# XOrduino-v1.net
KiCad netlist of a schematic drawn in EAGLE
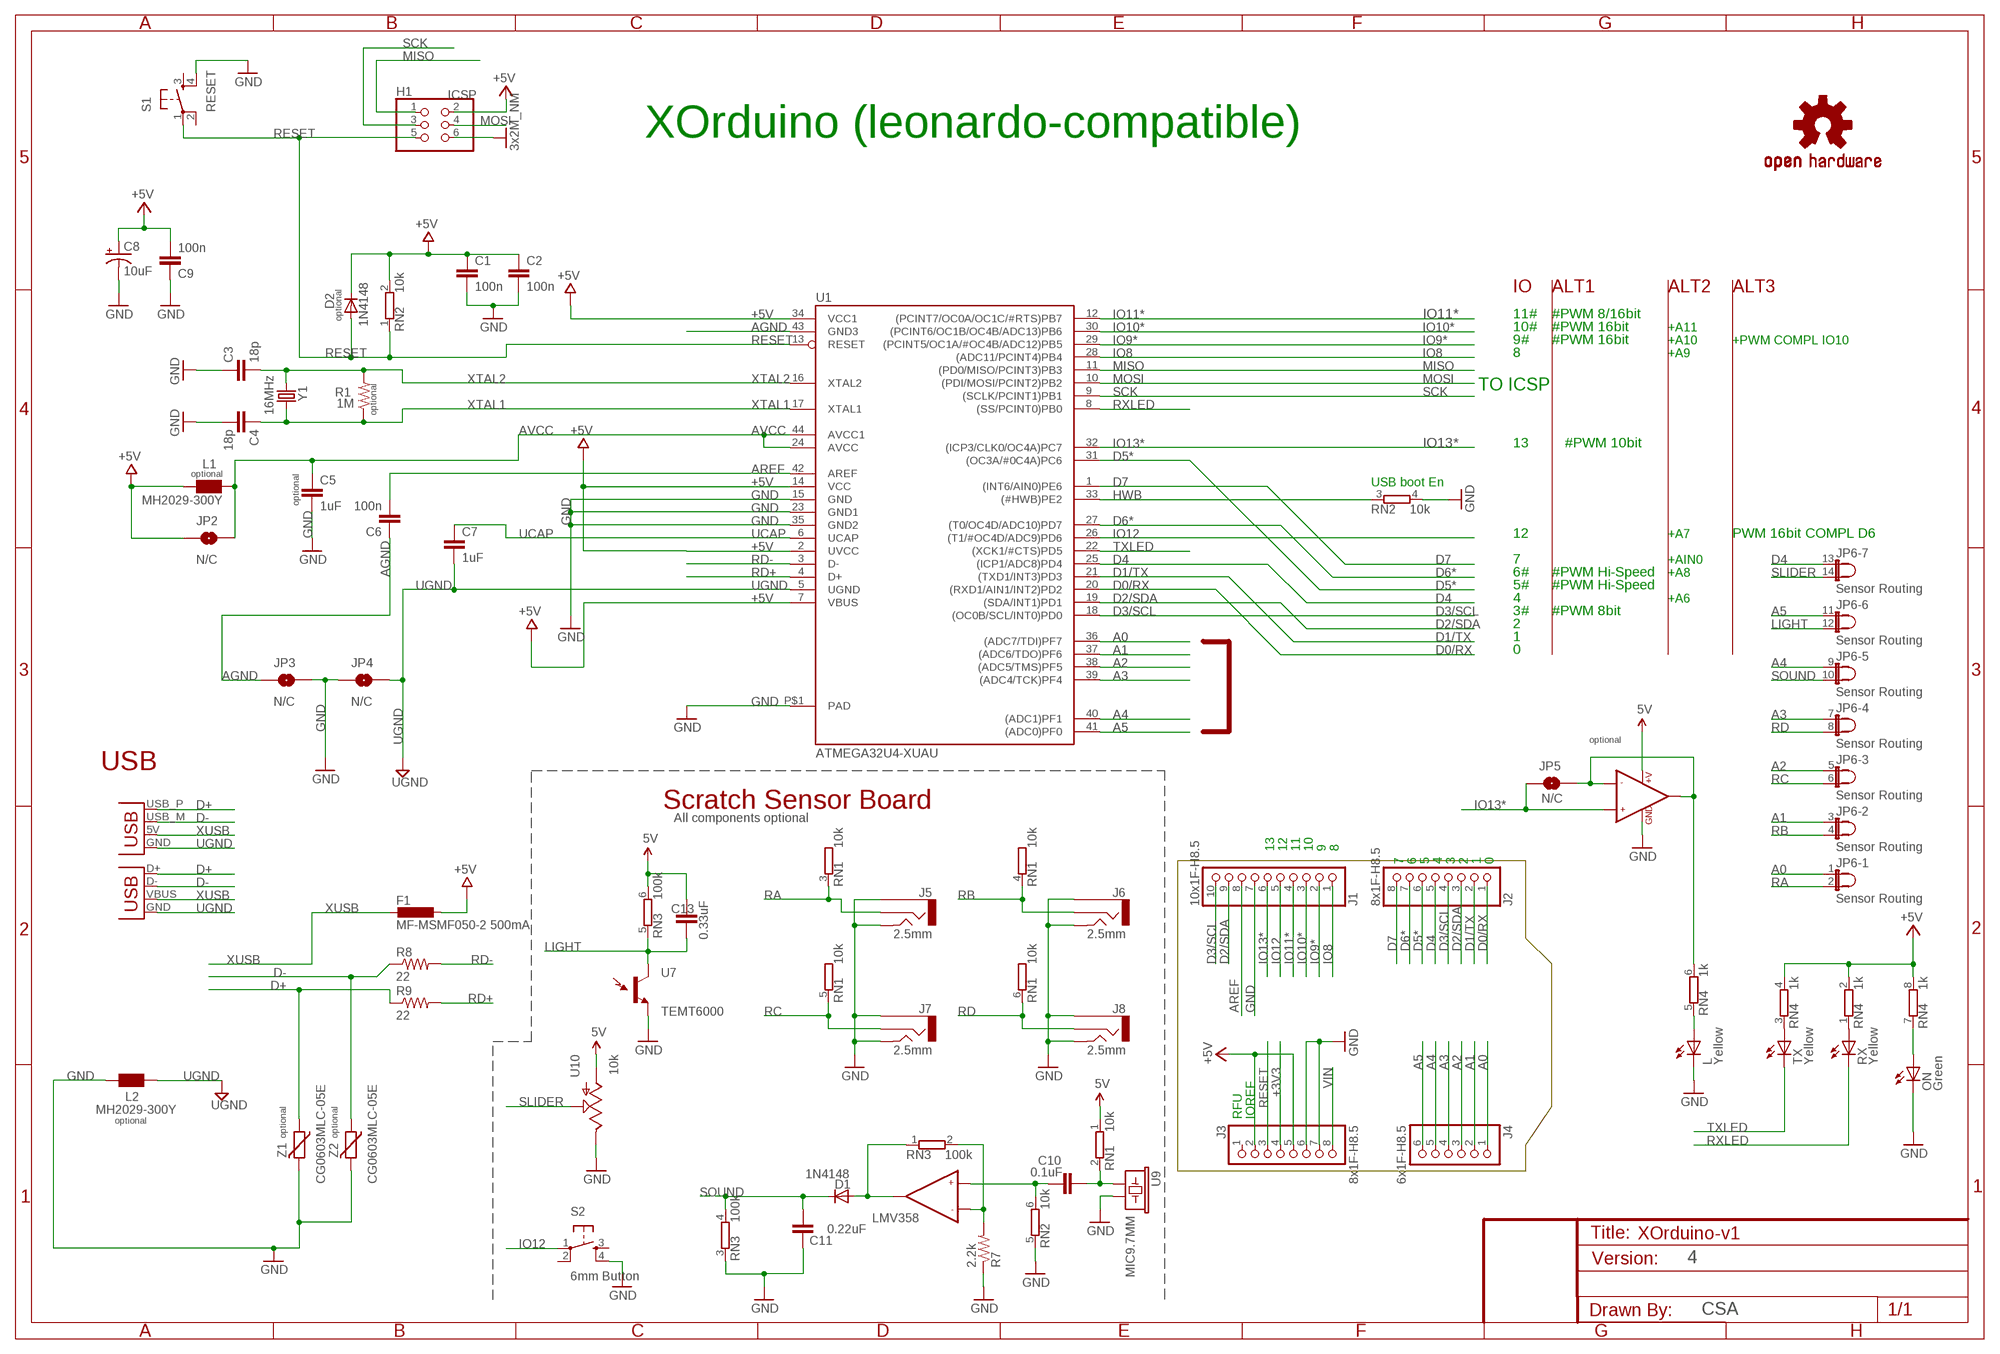
[diagram p0: schematic, sheet 1]

(export (version "E")
  (design (tool "Eeschema 10.0.6"))
  (components
    (comp (ref "C1")
      (value "100n")
      (footprint "eagle-import:CAP-PTH-SMALL")
      (libsource (lib "eagle-import") (part "CAPPTH"))
    )
    (comp (ref "C2")
      (value "100n")
      (footprint "eagle-import:CAP-PTH-SMALL")
      (libsource (lib "eagle-import") (part "CAPPTH"))
    )
    (comp (ref "C3")
      (value "18p")
      (footprint "eagle-import:CAP-PTH-SMALL")
      (libsource (lib "eagle-import") (part "CAPPTH"))
    )
    (comp (ref "C4")
      (value "18p")
      (footprint "eagle-import:CAP-PTH-SMALL")
      (libsource (lib "eagle-import") (part "CAPPTH"))
    )
    (comp (ref "C5")
      (value "1uF")
      (footprint "eagle-import:CAP-PTH-SMALL")
      (libsource (lib "eagle-import") (part "CAPPTH"))
    )
    (comp (ref "C6")
      (value "100n")
      (footprint "eagle-import:CAP-PTH-SMALL")
      (libsource (lib "eagle-import") (part "CAPPTH"))
    )
    (comp (ref "C7")
      (value "1uF")
      (footprint "eagle-import:CAP-PTH-SMALL")
      (libsource (lib "eagle-import") (part "CAPPTH"))
    )
    (comp (ref "C8")
      (value "10uF")
      (footprint "eagle-import:CPOL-RADIAL-10UF-25V")
      (libsource (lib "eagle-import") (part "CAP_POLPTH2"))
    )
    (comp (ref "C9")
      (value "100n")
      (footprint "eagle-import:CAP-PTH-SMALL")
      (libsource (lib "eagle-import") (part "CAPPTH"))
    )
    (comp (ref "C10")
      (value "0.1uF")
      (footprint "eagle-import:CAP-PTH-SMALL")
      (libsource (lib "eagle-import") (part "CAPPTH"))
    )
    (comp (ref "C11")
      (value "0.22uF")
      (footprint "eagle-import:CAP-PTH-SMALL")
      (libsource (lib "eagle-import") (part "CAPPTH"))
    )
    (comp (ref "C13")
      (value "0.33uF")
      (footprint "eagle-import:CAP-PTH-SMALL")
      (libsource (lib "eagle-import") (part "CAPPTH"))
    )
    (comp (ref "D1")
      (value "1N4148")
      (footprint "eagle-import:DIODE-1N4148")
      (libsource (lib "eagle-import") (part "DIODE1N4148"))
    )
    (comp (ref "D2")
      (value "1N4148")
      (footprint "eagle-import:DIODE-1N4148")
      (libsource (lib "eagle-import") (part "DIODE1N4148"))
    )
    (comp (ref "F1")
      (value "MF-MSMF050-2 500mA")
      (footprint "eagle-import:L1812")
      (libsource (lib "eagle-import") (part "L-EUL1812"))
    )
    (comp (ref "H1")
      (value "ICSP")
      (footprint "eagle-import:2X03")
      (libsource (lib "eagle-import") (part "PINHD-2X3"))
    )
    (comp (ref "J1")
      (value "10x1F-H8.5")
      (footprint "eagle-import:1X10")
      (libsource (lib "eagle-import") (part "PINHD-1X10"))
    )
    (comp (ref "J2")
      (value "8x1F-H8.5")
      (footprint "eagle-import:1X08")
      (libsource (lib "eagle-import") (part "PINHD-1X8"))
    )
    (comp (ref "J3")
      (value "8x1F-H8.5")
      (footprint "eagle-import:1X08")
      (libsource (lib "eagle-import") (part "PINHD-1X8"))
    )
    (comp (ref "J4")
      (value "6x1F-H8.5")
      (footprint "eagle-import:1X06")
      (libsource (lib "eagle-import") (part "PINHD-1X6"))
    )
    (comp (ref "J5")
      (value "2.5mm")
      (footprint "eagle-import:STEREOJACK2.5MM_SMD")
      (libsource (lib "eagle-import") (part "AUDIO-JACKSMD"))
    )
    (comp (ref "J6")
      (value "2.5mm")
      (footprint "eagle-import:STEREOJACK2.5MM_SMD")
      (libsource (lib "eagle-import") (part "AUDIO-JACKSMD"))
    )
    (comp (ref "J7")
      (value "2.5mm")
      (footprint "eagle-import:STEREOJACK2.5MM_SMD")
      (libsource (lib "eagle-import") (part "AUDIO-JACKSMD"))
    )
    (comp (ref "J8")
      (value "2.5mm")
      (footprint "eagle-import:STEREOJACK2.5MM_SMD")
      (libsource (lib "eagle-import") (part "AUDIO-JACKSMD"))
    )
    (comp (ref "JP2")
      (value "N/C")
      (footprint "eagle-import:SJ_2S-TRACE")
      (libsource (lib "eagle-import") (part "SOLDERJUMPERTRACE"))
    )
    (comp (ref "JP3")
      (value "N/C")
      (footprint "eagle-import:SJ_2S-TRACE")
      (libsource (lib "eagle-import") (part "SOLDERJUMPERTRACE"))
    )
    (comp (ref "JP4")
      (value "N/C")
      (footprint "eagle-import:SJ_2S-TRACE")
      (libsource (lib "eagle-import") (part "SOLDERJUMPERTRACE"))
    )
    (comp (ref "JP5")
      (value "N/C")
      (footprint "eagle-import:SJ_2S-TRACE")
      (libsource (lib "eagle-import") (part "SOLDERJUMPERTRACE"))
    )
    (comp (ref "JP6")
      (value "Sensor Routing")
      (footprint "eagle-import:JP7QS")
      (libsource (lib "eagle-import") (part "JP7QES"))
    )
    (comp (ref "L")
      (value "Yellow")
      (footprint "eagle-import:LED3MM")
      (libsource (lib "eagle-import") (part "LED3MM"))
    )
    (comp (ref "L1")
      (value "MH2029-300Y")
      (footprint "eagle-import:0805")
      (libsource (lib "eagle-import") (part "WE-CBF_0805"))
    )
    (comp (ref "L2")
      (value "MH2029-300Y")
      (footprint "eagle-import:0805")
      (libsource (lib "eagle-import") (part "WE-CBF_0805"))
    )
    (comp (ref "ON")
      (value "Green")
      (footprint "eagle-import:LED3MM")
      (libsource (lib "eagle-import") (part "LED3MM"))
    )
    (comp (ref "R1")
      (value "1M")
      (footprint "eagle-import:AXIAL-0.3")
      (libsource (lib "eagle-import") (part "RESISTORAXIAL-0.3"))
    )
    (comp (ref "R7")
      (value "2.2k")
      (footprint "eagle-import:AXIAL-0.3")
      (libsource (lib "eagle-import") (part "RESISTORAXIAL-0.3"))
    )
    (comp (ref "R8")
      (value "22")
      (footprint "eagle-import:AXIAL-0.3")
      (libsource (lib "eagle-import") (part "RESISTORAXIAL-0.3"))
    )
    (comp (ref "R9")
      (value "22")
      (footprint "eagle-import:AXIAL-0.3")
      (libsource (lib "eagle-import") (part "RESISTORAXIAL-0.3"))
    )
    (comp (ref "RN1")
      (value "10k")
      (footprint "eagle-import:SIL6")
      (libsource (lib "eagle-import") (part "GE05RP"))
    )
    (comp (ref "RN2")
      (value "10k")
      (footprint "eagle-import:SIL6")
      (libsource (lib "eagle-import") (part "E3RP"))
    )
    (comp (ref "RN3")
      (value "100k")
      (footprint "eagle-import:SIL6")
      (libsource (lib "eagle-import") (part "E3RP"))
    )
    (comp (ref "RN4")
      (value "1k")
      (footprint "eagle-import:SIL8")
      (libsource (lib "eagle-import") (part "E4RP"))
    )
    (comp (ref "RX")
      (value "Yellow")
      (footprint "eagle-import:LED3MM")
      (libsource (lib "eagle-import") (part "LED3MM"))
    )
    (comp (ref "S1")
      (value "RESET")
      (footprint "eagle-import:TACTILE-PTH")
      (libsource (lib "eagle-import") (part "TAC_SWITCHPTH"))
    )
    (comp (ref "S2")
      (value "6mm Button")
      (footprint "eagle-import:TACTILE-PTH")
      (libsource (lib "eagle-import") (part "TAC_SWITCHPTH"))
    )
    (comp (ref "TX")
      (value "Yellow")
      (footprint "eagle-import:LED3MM")
      (libsource (lib "eagle-import") (part "LED3MM"))
    )
    (comp (ref "U$5")
      (value "OSHW-LOGOL")
      (footprint "eagle-import:OSHW-LOGO-L")
      (libsource (lib "eagle-import") (part "OSHW-LOGOL"))
    )
    (comp (ref "U1")
      (value "ATMEGA32U4-XUAU")
      (footprint "eagle-import:TQFP44-PAD")
      (libsource (lib "eagle-import") (part "ATMEGA32U4-XUAU"))
    )
    (comp (ref "U7")
      (value "TEMT6000")
      (footprint "eagle-import:TEMT6000-SEN")
      (libsource (lib "eagle-import") (part "TEMT6000"))
    )
    (comp (ref "U8")
      (value "LMV358")
      (footprint "eagle-import:SO08")
      (libsource (lib "eagle-import") (part "LMV358"))
    )
    (comp (ref "U9")
      (value "MIC9.7MM")
      (footprint "eagle-import:MIC-9.7MM")
      (libsource (lib "eagle-import") (part "MIC9.7MM"))
    )
    (comp (ref "U10")
      (value "10k")
      (footprint "eagle-import:ALPS_POT")
      (libsource (lib "eagle-import") (part "POT"))
    )
    (comp (ref "X1")
      (value "USBPCB")
      (footprint "eagle-import:USB-A-PCB")
      (libsource (lib "eagle-import") (part "USBPCB"))
    )
    (comp (ref "X2")
      (value "USB")
      (footprint "eagle-import:USB-MB-H2")
      (libsource (lib "eagle-import") (part "USB"))
    )
    (comp (ref "Y1")
      (value "16MHz")
      (footprint "eagle-import:HC49US")
      (libsource (lib "eagle-import") (part "CRYSTALHC49US"))
    )
    (comp (ref "Z1")
      (value "CG0603MLC-05E")
      (footprint "eagle-import:CT_CN0603")
      (libsource (lib "eagle-import") (part "VARISTORCN0603"))
    )
    (comp (ref "Z2")
      (value "CG0603MLC-05E")
      (footprint "eagle-import:CT_CN0603")
      (libsource (lib "eagle-import") (part "VARISTORCN0603"))
    )
  )
  (nets
    (net (code "1") (name "+5V") (class "Default")
      (node (ref "C1") (pin "1") (pinfunction "1_1") (pintype "passive"))
      (node (ref "C2") (pin "1") (pinfunction "1_1") (pintype "passive"))
      (node (ref "C8") (pin "1") (pinfunction "+_1") (pintype "passive"))
      (node (ref "C9") (pin "2") (pinfunction "2_2") (pintype "passive"))
      (node (ref "D2") (pin "C") (pinfunction "C_C") (pintype "passive"))
      (node (ref "F1") (pin "1") (pinfunction "1_1") (pintype "passive"))
      (node (ref "H1") (pin "2") (pinfunction "2_2") (pintype "passive"))
      (node (ref "J3") (pin "2") (pinfunction "2_2") (pintype "passive"))
      (node (ref "J3") (pin "5") (pinfunction "5_5") (pintype "passive"))
      (node (ref "JP2") (pin "1") (pinfunction "1_1") (pintype "passive"))
      (node (ref "L1") (pin "1") (pinfunction "1_1") (pintype "passive"))
      (node (ref "RN2") (pin "2") (pinfunction "2_2") (pintype "passive"))
      (node (ref "RN4") (pin "2") (pinfunction "2_2") (pintype "passive"))
      (node (ref "RN4") (pin "4") (pinfunction "2_4") (pintype "passive"))
      (node (ref "RN4") (pin "8") (pinfunction "2_8") (pintype "passive"))
      (node (ref "U1") (pin "14") (pinfunction "VCC_14") (pintype "power_in"))
      (node (ref "U1") (pin "2") (pinfunction "UVCC_2") (pintype "power_in"))
      (node (ref "U1") (pin "34") (pinfunction "VCC1_34") (pintype "power_in"))
      (node (ref "U1") (pin "7") (pinfunction "VBUS_7") (pintype "input"))
    )
    (net (code "2") (name "/+3V3") (class "Default")
      (node (ref "J3") (pin "4") (pinfunction "4_4") (pintype "passive"))
    )
    (net (code "3") (name "/A0") (class "Default")
      (node (ref "J4") (pin "1") (pinfunction "1_1") (pintype "passive"))
      (node (ref "JP6") (pin "1") (pinfunction "1_1") (pintype "passive"))
      (node (ref "U1") (pin "36") (pinfunction "(ADC7/TDI)PF7_36") (pintype "bidirectional"))
    )
    (net (code "4") (name "/A1") (class "Default")
      (node (ref "J4") (pin "2") (pinfunction "2_2") (pintype "passive"))
      (node (ref "JP6") (pin "3") (pinfunction "1_3") (pintype "passive"))
      (node (ref "U1") (pin "37") (pinfunction "(ADC6/TDO)PF6_37") (pintype "bidirectional"))
    )
    (net (code "5") (name "/A2") (class "Default")
      (node (ref "J4") (pin "3") (pinfunction "3_3") (pintype "passive"))
      (node (ref "JP6") (pin "5") (pinfunction "1_5") (pintype "passive"))
      (node (ref "U1") (pin "38") (pinfunction "(ADC5/TMS)PF5_38") (pintype "bidirectional"))
    )
    (net (code "6") (name "/A3") (class "Default")
      (node (ref "J4") (pin "4") (pinfunction "4_4") (pintype "passive"))
      (node (ref "JP6") (pin "7") (pinfunction "1_7") (pintype "passive"))
      (node (ref "U1") (pin "39") (pinfunction "(ADC4/TCK)PF4_39") (pintype "bidirectional"))
    )
    (net (code "7") (name "/A4") (class "Default")
      (node (ref "J4") (pin "5") (pinfunction "5_5") (pintype "passive"))
      (node (ref "JP6") (pin "9") (pinfunction "1_9") (pintype "passive"))
      (node (ref "U1") (pin "40") (pinfunction "(ADC1)PF1_40") (pintype "bidirectional"))
    )
    (net (code "8") (name "/A5") (class "Default")
      (node (ref "J4") (pin "6") (pinfunction "6_6") (pintype "passive"))
      (node (ref "JP6") (pin "11") (pinfunction "1_11") (pintype "passive"))
      (node (ref "U1") (pin "41") (pinfunction "(ADC0)PF0_41") (pintype "bidirectional"))
    )
    (net (code "9") (name "/AGND") (class "Default")
      (node (ref "C6") (pin "1") (pinfunction "1_1") (pintype "passive"))
      (node (ref "JP3") (pin "1") (pinfunction "1_1") (pintype "passive"))
      (node (ref "U1") (pin "43") (pinfunction "GND3_43") (pintype "power_in"))
    )
    (net (code "10") (name "/AREF") (class "Default")
      (node (ref "C6") (pin "2") (pinfunction "2_2") (pintype "passive"))
      (node (ref "J1") (pin "8") (pinfunction "8_8") (pintype "passive"))
      (node (ref "U1") (pin "42") (pinfunction "AREF_42") (pintype "power_in"))
    )
    (net (code "11") (name "/AVCC") (class "Default")
      (node (ref "C5") (pin "1") (pinfunction "1_1") (pintype "passive"))
      (node (ref "JP2") (pin "2") (pinfunction "2_2") (pintype "passive"))
      (node (ref "L1") (pin "2") (pinfunction "2_2") (pintype "passive"))
      (node (ref "U1") (pin "24") (pinfunction "AVCC_24") (pintype "power_in"))
      (node (ref "U1") (pin "44") (pinfunction "AVCC1_44") (pintype "power_in"))
    )
    (net (code "12") (name "/D+") (class "Default")
      (node (ref "R9") (pin "P$1") (pinfunction "1_P$1") (pintype "passive"))
      (node (ref "X1") (pin "USB_P") (pinfunction "D+_USB_P") (pintype "bidirectional"))
      (node (ref "X2") (pin "D+") (pinfunction "D+_D+") (pintype "bidirectional"))
      (node (ref "Z1") (pin "1") (pinfunction "1_1") (pintype "passive"))
    )
    (net (code "13") (name "/D-") (class "Default")
      (node (ref "R8") (pin "P$1") (pinfunction "1_P$1") (pintype "passive"))
      (node (ref "X1") (pin "USB_M") (pinfunction "D-_USB_M") (pintype "bidirectional"))
      (node (ref "X2") (pin "D-") (pinfunction "D-_D-") (pintype "bidirectional"))
      (node (ref "Z2") (pin "1") (pinfunction "1_1") (pintype "passive"))
    )
    (net (code "14") (name "/D0{slash}RX") (class "Default")
      (node (ref "J2") (pin "1") (pinfunction "1_1") (pintype "passive"))
      (node (ref "U1") (pin "20") (pinfunction "(RXD1/AIN1/INT2)PD2_20") (pintype "bidirectional"))
    )
    (net (code "15") (name "/D1{slash}TX") (class "Default")
      (node (ref "J2") (pin "2") (pinfunction "2_2") (pintype "passive"))
      (node (ref "U1") (pin "21") (pinfunction "(TXD1/INT3)PD3_21") (pintype "bidirectional"))
    )
    (net (code "16") (name "/D2{slash}SDA") (class "Default")
      (node (ref "J1") (pin "9") (pinfunction "9_9") (pintype "passive"))
      (node (ref "J2") (pin "3") (pinfunction "3_3") (pintype "passive"))
      (node (ref "U1") (pin "19") (pinfunction "(SDA/INT1)PD1_19") (pintype "bidirectional"))
    )
    (net (code "17") (name "/D3{slash}SCL") (class "Default")
      (node (ref "J1") (pin "10") (pinfunction "10_10") (pintype "passive"))
      (node (ref "J2") (pin "4") (pinfunction "4_4") (pintype "passive"))
      (node (ref "U1") (pin "18") (pinfunction "(OC0B/SCL/INT0)PD0_18") (pintype "bidirectional"))
    )
    (net (code "18") (name "/D4") (class "Default")
      (node (ref "J2") (pin "5") (pinfunction "5_5") (pintype "passive"))
      (node (ref "JP6") (pin "13") (pinfunction "1_13") (pintype "passive"))
      (node (ref "U1") (pin "25") (pinfunction "(ICP1/ADC8)PD4_25") (pintype "bidirectional"))
    )
    (net (code "19") (name "/D5*") (class "Default")
      (node (ref "J2") (pin "6") (pinfunction "6_6") (pintype "passive"))
      (node (ref "U1") (pin "31") (pinfunction "(OC3A/#0C4A)PC6_31") (pintype "bidirectional"))
    )
    (net (code "20") (name "/D6*") (class "Default")
      (node (ref "J2") (pin "7") (pinfunction "7_7") (pintype "passive"))
      (node (ref "U1") (pin "27") (pinfunction "(T0/OC4D/ADC10)PD7_27") (pintype "bidirectional"))
    )
    (net (code "21") (name "/D7") (class "Default")
      (node (ref "J2") (pin "8") (pinfunction "8_8") (pintype "passive"))
      (node (ref "U1") (pin "1") (pinfunction "(INT6/AIN0)PE6_1") (pintype "bidirectional"))
    )
    (net (code "22") (name "/HWB") (class "Default")
      (node (ref "RN2") (pin "3") (pinfunction "1_3") (pintype "passive"))
      (node (ref "U1") (pin "33") (pinfunction "(#HWB)PE2_33") (pintype "bidirectional"))
    )
    (net (code "23") (name "/IO8") (class "Default")
      (node (ref "J1") (pin "1") (pinfunction "1_1") (pintype "passive"))
      (node (ref "U1") (pin "28") (pinfunction "(ADC11/PCINT4)PB4_28") (pintype "bidirectional"))
    )
    (net (code "24") (name "/IO9*") (class "Default")
      (node (ref "J1") (pin "2") (pinfunction "2_2") (pintype "passive"))
      (node (ref "U1") (pin "29") (pinfunction "(PCINT5/OC1A/#OC4B/ADC12)PB5_29") (pintype "bidirectional"))
    )
    (net (code "25") (name "/IO10*") (class "Default")
      (node (ref "J1") (pin "3") (pinfunction "3_3") (pintype "passive"))
      (node (ref "U1") (pin "30") (pinfunction "(PCINT6/OC1B/OC4B/ADC13)PB6_30") (pintype "bidirectional"))
    )
    (net (code "26") (name "/IO11*") (class "Default")
      (node (ref "J1") (pin "4") (pinfunction "4_4") (pintype "passive"))
      (node (ref "U1") (pin "12") (pinfunction "(PCINT7/OC0A/OC1C/#RTS)PB7_12") (pintype "bidirectional"))
    )
    (net (code "27") (name "/IO12") (class "Default")
      (node (ref "J1") (pin "5") (pinfunction "5_5") (pintype "passive"))
      (node (ref "S2") (pin "1") (pinfunction "1_1") (pintype "passive"))
      (node (ref "U1") (pin "26") (pinfunction "(T1/#OC4D/ADC9)PD6_26") (pintype "bidirectional"))
    )
    (net (code "28") (name "/IO13*") (class "Default")
      (node (ref "J1") (pin "6") (pinfunction "6_6") (pintype "passive"))
      (node (ref "JP5") (pin "1") (pinfunction "1_1") (pintype "passive"))
      (node (ref "U1") (pin "32") (pinfunction "(ICP3/CLK0/OC4A)PC7_32") (pintype "bidirectional"))
      (node (ref "U8") (pin "3") (pinfunction "+IN1_3") (pintype "input"))
    )
    (net (code "29") (name "/LIGHT") (class "Default")
      (node (ref "C13") (pin "2") (pinfunction "2_2") (pintype "passive"))
      (node (ref "JP6") (pin "12") (pinfunction "2_12") (pintype "passive"))
      (node (ref "RN3") (pin "5") (pinfunction "1_5") (pintype "passive"))
      (node (ref "U7") (pin "COLLECTOR") (pinfunction "C1_COLLECTOR") (pintype "passive"))
    )
    (net (code "30") (name "/MISO") (class "Default")
      (node (ref "H1") (pin "1") (pinfunction "1_1") (pintype "passive"))
      (node (ref "U1") (pin "11") (pinfunction "(PD0/MISO/PCINT3)PB3_11") (pintype "bidirectional"))
    )
    (net (code "31") (name "/MOSI") (class "Default")
      (node (ref "H1") (pin "4") (pinfunction "4_4") (pintype "passive"))
      (node (ref "U1") (pin "10") (pinfunction "(PDI/MOSI/PCINT2)PB2_10") (pintype "bidirectional"))
    )
    (net (code "32") (name "/RA") (class "Default")
      (node (ref "J5") (pin "4") (pinfunction "2_4") (pintype "bidirectional"))
      (node (ref "JP6") (pin "2") (pinfunction "2_2") (pintype "passive"))
      (node (ref "RN1") (pin "3") (pinfunction "2_3") (pintype "passive"))
    )
    (net (code "33") (name "/RB") (class "Default")
      (node (ref "J6") (pin "4") (pinfunction "2_4") (pintype "bidirectional"))
      (node (ref "JP6") (pin "4") (pinfunction "2_4") (pintype "passive"))
      (node (ref "RN1") (pin "4") (pinfunction "2_4") (pintype "passive"))
    )
    (net (code "34") (name "/RC") (class "Default")
      (node (ref "J7") (pin "4") (pinfunction "2_4") (pintype "bidirectional"))
      (node (ref "JP6") (pin "6") (pinfunction "2_6") (pintype "passive"))
      (node (ref "RN1") (pin "5") (pinfunction "2_5") (pintype "passive"))
    )
    (net (code "35") (name "/RD") (class "Default")
      (node (ref "J8") (pin "4") (pinfunction "2_4") (pintype "bidirectional"))
      (node (ref "JP6") (pin "8") (pinfunction "2_8") (pintype "passive"))
      (node (ref "RN1") (pin "6") (pinfunction "2_6") (pintype "passive"))
    )
    (net (code "36") (name "/RD+") (class "Default")
      (node (ref "R9") (pin "P$2") (pinfunction "2_P$2") (pintype "passive"))
      (node (ref "U1") (pin "4") (pinfunction "D+_4") (pintype "bidirectional"))
    )
    (net (code "37") (name "/RD-") (class "Default")
      (node (ref "R8") (pin "P$2") (pinfunction "2_P$2") (pintype "passive"))
      (node (ref "U1") (pin "3") (pinfunction "D-_3") (pintype "bidirectional"))
    )
    (net (code "38") (name "/RESET") (class "Default")
      (node (ref "D2") (pin "A") (pinfunction "A_A") (pintype "passive"))
      (node (ref "H1") (pin "5") (pinfunction "5_5") (pintype "passive"))
      (node (ref "J3") (pin "3") (pinfunction "3_3") (pintype "passive"))
      (node (ref "RN2") (pin "1") (pinfunction "1_1") (pintype "passive"))
      (node (ref "S1") (pin "1") (pinfunction "1_1") (pintype "passive"))
      (node (ref "U1") (pin "13") (pinfunction "RESET_13") (pintype "input"))
    )
    (net (code "39") (name "/RXLED") (class "Default")
      (node (ref "RX") (pin "K") (pinfunction "C_K") (pintype "passive"))
      (node (ref "U1") (pin "8") (pinfunction "(SS/PCINT0)PB0_8") (pintype "bidirectional"))
    )
    (net (code "40") (name "/SCK") (class "Default")
      (node (ref "H1") (pin "3") (pinfunction "3_3") (pintype "passive"))
      (node (ref "U1") (pin "9") (pinfunction "(SCLK/PCINT1)PB1_9") (pintype "bidirectional"))
    )
    (net (code "41") (name "/SLIDER") (class "Default")
      (node (ref "JP6") (pin "14") (pinfunction "2_14") (pintype "passive"))
      (node (ref "U10") (pin "P$2") (pinfunction "S_P$2") (pintype "passive"))
    )
    (net (code "42") (name "/SOUND") (class "Default")
      (node (ref "C11") (pin "2") (pinfunction "2_2") (pintype "passive"))
      (node (ref "D1") (pin "C") (pinfunction "C_C") (pintype "passive"))
      (node (ref "JP6") (pin "10") (pinfunction "2_10") (pintype "passive"))
      (node (ref "RN3") (pin "4") (pinfunction "2_4") (pintype "passive"))
    )
    (net (code "43") (name "/TXLED") (class "Default")
      (node (ref "TX") (pin "K") (pinfunction "C_K") (pintype "passive"))
      (node (ref "U1") (pin "22") (pinfunction "(XCK1/#CTS)PD5_22") (pintype "bidirectional"))
    )
    (net (code "44") (name "/UCAP") (class "Default")
      (node (ref "C7") (pin "1") (pinfunction "1_1") (pintype "passive"))
      (node (ref "U1") (pin "6") (pinfunction "UCAP_6") (pintype "passive"))
    )
    (net (code "45") (name "/VIN") (class "Default")
      (node (ref "J3") (pin "8") (pinfunction "8_8") (pintype "passive"))
    )
    (net (code "46") (name "/XTAL1") (class "Default")
      (node (ref "C4") (pin "1") (pinfunction "1_1") (pintype "passive"))
      (node (ref "R1") (pin "P$1") (pinfunction "1_P$1") (pintype "passive"))
      (node (ref "U1") (pin "17") (pinfunction "XTAL1_17") (pintype "bidirectional"))
      (node (ref "Y1") (pin "2") (pinfunction "2_2") (pintype "passive"))
    )
    (net (code "47") (name "/XTAL2") (class "Default")
      (node (ref "C3") (pin "2") (pinfunction "2_2") (pintype "passive"))
      (node (ref "R1") (pin "P$2") (pinfunction "2_P$2") (pintype "passive"))
      (node (ref "U1") (pin "16") (pinfunction "XTAL2_16") (pintype "bidirectional"))
      (node (ref "Y1") (pin "1") (pinfunction "1_1") (pintype "passive"))
    )
    (net (code "48") (name "/XUSB") (class "Default")
      (node (ref "F1") (pin "2") (pinfunction "2_2") (pintype "passive"))
      (node (ref "X1") (pin "5V") (pinfunction "VBUS_5V") (pintype "bidirectional"))
      (node (ref "X2") (pin "VBUS") (pinfunction "VBUS_VBUS") (pintype "bidirectional"))
    )
    (net (code "49") (name "3x2M_NM") (class "Default")
      (node (ref "C1") (pin "2") (pinfunction "2_2") (pintype "passive"))
      (node (ref "C11") (pin "1") (pinfunction "1_1") (pintype "passive"))
      (node (ref "C2") (pin "2") (pinfunction "2_2") (pintype "passive"))
      (node (ref "C3") (pin "1") (pinfunction "1_1") (pintype "passive"))
      (node (ref "C4") (pin "2") (pinfunction "2_2") (pintype "passive"))
      (node (ref "C5") (pin "2") (pinfunction "2_2") (pintype "passive"))
      (node (ref "C8") (pin "2") (pinfunction "-_2") (pintype "passive"))
      (node (ref "C9") (pin "1") (pinfunction "1_1") (pintype "passive"))
      (node (ref "H1") (pin "6") (pinfunction "6_6") (pintype "passive"))
      (node (ref "J1") (pin "7") (pinfunction "7_7") (pintype "passive"))
      (node (ref "J3") (pin "6") (pinfunction "6_6") (pintype "passive"))
      (node (ref "J3") (pin "7") (pinfunction "7_7") (pintype "passive"))
      (node (ref "J5") (pin "1") (pinfunction "5_1") (pintype "bidirectional"))
      (node (ref "J5") (pin "5") (pinfunction "1_5") (pintype "bidirectional"))
      (node (ref "J6") (pin "1") (pinfunction "5_1") (pintype "bidirectional"))
      (node (ref "J6") (pin "5") (pinfunction "1_5") (pintype "bidirectional"))
      (node (ref "J7") (pin "1") (pinfunction "5_1") (pintype "bidirectional"))
      (node (ref "J7") (pin "5") (pinfunction "1_5") (pintype "bidirectional"))
      (node (ref "J8") (pin "1") (pinfunction "5_1") (pintype "bidirectional"))
      (node (ref "J8") (pin "5") (pinfunction "1_5") (pintype "bidirectional"))
      (node (ref "JP3") (pin "2") (pinfunction "2_2") (pintype "passive"))
      (node (ref "JP4") (pin "1") (pinfunction "1_1") (pintype "passive"))
      (node (ref "L") (pin "K") (pinfunction "C_K") (pintype "passive"))
      (node (ref "L2") (pin "2") (pinfunction "2_2") (pintype "passive"))
      (node (ref "ON") (pin "K") (pinfunction "C_K") (pintype "passive"))
      (node (ref "R7") (pin "P$1") (pinfunction "1_P$1") (pintype "passive"))
      (node (ref "RN2") (pin "4") (pinfunction "2_4") (pintype "passive"))
      (node (ref "RN2") (pin "5") (pinfunction "1_5") (pintype "passive"))
      (node (ref "RN3") (pin "3") (pinfunction "1_3") (pintype "passive"))
      (node (ref "S1") (pin "4") (pinfunction "4_4") (pintype "passive"))
      (node (ref "S2") (pin "4") (pinfunction "4_4") (pintype "passive"))
      (node (ref "U1") (pin "15") (pinfunction "GND_15") (pintype "power_in"))
      (node (ref "U1") (pin "23") (pinfunction "GND1_23") (pintype "power_in"))
      (node (ref "U1") (pin "35") (pinfunction "GND2_35") (pintype "power_in"))
      (node (ref "U1") (pin "P$1") (pinfunction "PAD_P$1") (pintype "power_in"))
      (node (ref "U10") (pin "P$1") (pinfunction "E_P$1") (pintype "passive"))
      (node (ref "U7") (pin "EMITTER") (pinfunction "E1_EMITTER") (pintype "passive"))
      (node (ref "U8") (pin "4") (pinfunction "GND_4") (pintype "power_in"))
      (node (ref "U9") (pin "2") (pinfunction "2_2") (pintype "passive"))
      (node (ref "Z1") (pin "2") (pinfunction "2_2") (pintype "passive"))
      (node (ref "Z2") (pin "2") (pinfunction "2_2") (pintype "passive"))
    )
    (net (code "50") (name "5V") (class "Default")
      (node (ref "C13") (pin "1") (pinfunction "1_1") (pintype "passive"))
      (node (ref "RN1") (pin "1") (pinfunction "1_1") (pintype "passive"))
      (node (ref "RN3") (pin "6") (pinfunction "2_6") (pintype "passive"))
      (node (ref "U10") (pin "P$3") (pinfunction "A_P$3") (pintype "passive"))
      (node (ref "U8") (pin "8") (pinfunction "+V_8") (pintype "power_in"))
    )
    (net (code "51") (name "Net-(C10-Pad1)") (class "Default")
      (node (ref "C10") (pin "1") (pinfunction "1_1") (pintype "passive"))
      (node (ref "RN1") (pin "2") (pinfunction "2_2") (pintype "passive"))
      (node (ref "U9") (pin "1") (pinfunction "1_1") (pintype "passive"))
    )
    (net (code "52") (name "Net-(R7-2)") (class "Default")
      (node (ref "R7") (pin "P$2") (pinfunction "2_P$2") (pintype "passive"))
      (node (ref "RN3") (pin "2") (pinfunction "2_2") (pintype "passive"))
      (node (ref "U8") (pin "6") (pinfunction "-IN2_6") (pintype "input"))
    )
    (net (code "53") (name "Net-(RN2C-2)") (class "Default")
      (node (ref "C10") (pin "2") (pinfunction "2_2") (pintype "passive"))
      (node (ref "RN2") (pin "6") (pinfunction "2_6") (pintype "passive"))
      (node (ref "U8") (pin "5") (pinfunction "+IN2_5") (pintype "input"))
    )
    (net (code "54") (name "Net-(RN4-Pad1)") (class "Default")
      (node (ref "RN4") (pin "1") (pinfunction "1_1") (pintype "passive"))
      (node (ref "RX") (pin "A") (pinfunction "A_A") (pintype "passive"))
    )
    (net (code "55") (name "Net-(RN4B-1)") (class "Default")
      (node (ref "RN4") (pin "3") (pinfunction "1_3") (pintype "passive"))
      (node (ref "TX") (pin "A") (pinfunction "A_A") (pintype "passive"))
    )
    (net (code "56") (name "Net-(RN4C-1)") (class "Default")
      (node (ref "L") (pin "A") (pinfunction "A_A") (pintype "passive"))
      (node (ref "RN4") (pin "5") (pinfunction "1_5") (pintype "passive"))
    )
    (net (code "57") (name "Net-(RN4C-2)") (class "Default")
      (node (ref "JP5") (pin "2") (pinfunction "2_2") (pintype "passive"))
      (node (ref "RN4") (pin "6") (pinfunction "2_6") (pintype "passive"))
      (node (ref "U8") (pin "1") (pinfunction "OUT1_1") (pintype "output"))
      (node (ref "U8") (pin "2") (pinfunction "-IN1_2") (pintype "input"))
    )
    (net (code "58") (name "Net-(RN4D-1)") (class "Default")
      (node (ref "ON") (pin "A") (pinfunction "A_A") (pintype "passive"))
      (node (ref "RN4") (pin "7") (pinfunction "1_7") (pintype "passive"))
    )
    (net (code "59") (name "Net-(U8B-OUT2)") (class "Default")
      (node (ref "D1") (pin "A") (pinfunction "A_A") (pintype "passive"))
      (node (ref "RN3") (pin "1") (pinfunction "1_1") (pintype "passive"))
      (node (ref "U8") (pin "7") (pinfunction "OUT2_7") (pintype "output"))
    )
    (net (code "60") (name "UGND") (class "Default")
      (node (ref "C7") (pin "2") (pinfunction "2_2") (pintype "passive"))
      (node (ref "JP4") (pin "2") (pinfunction "2_2") (pintype "passive"))
      (node (ref "L2") (pin "1") (pinfunction "1_1") (pintype "passive"))
      (node (ref "U1") (pin "5") (pinfunction "UGND_5") (pintype "power_in"))
      (node (ref "X1") (pin "GND") (pinfunction "GND_GND") (pintype "bidirectional"))
      (node (ref "X2") (pin "GND") (pinfunction "GND_GND") (pintype "bidirectional"))
    )
    (net (code "61") (name "unconnected-(J3-Pad1)") (class "Default")
      (node (ref "J3") (pin "1") (pinfunction "1_1") (pintype "passive"))
    )
    (net (code "62") (name "unconnected-(S1-Pad2)") (class "Default")
      (node (ref "S1") (pin "2") (pinfunction "2_2") (pintype "passive"))
    )
    (net (code "63") (name "unconnected-(S1-Pad3)") (class "Default")
      (node (ref "S1") (pin "3") (pinfunction "3_3") (pintype "passive"))
    )
    (net (code "64") (name "unconnected-(S2-Pad2)") (class "Default")
      (node (ref "S2") (pin "2") (pinfunction "2_2") (pintype "passive"))
    )
    (net (code "65") (name "unconnected-(S2-Pad3)") (class "Default")
      (node (ref "S2") (pin "3") (pinfunction "3_3") (pintype "passive"))
    )
  )
)
